# MCU.net
KiCad netlist of a schematic drawn in Altium Designer
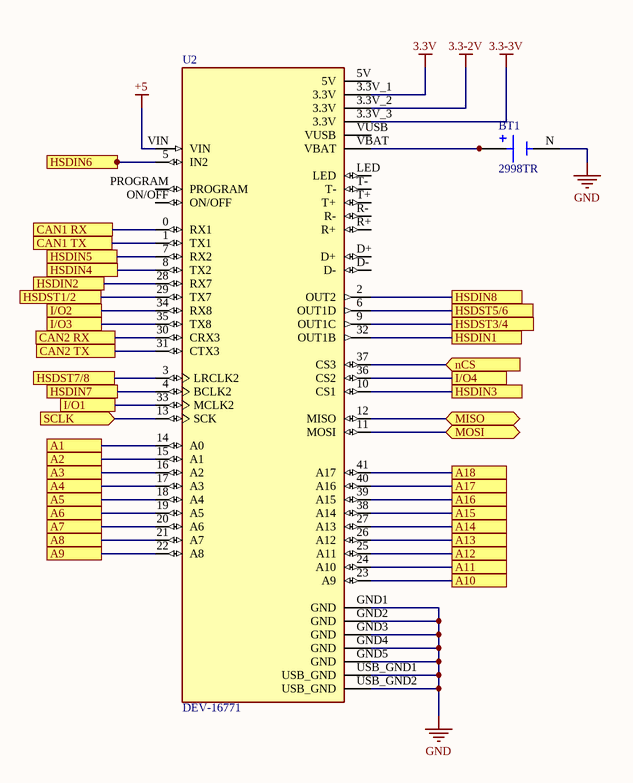
[diagram p0: MCU.SchDoc]

(export (version "E")
  (design (tool "Eeschema 10.0.6"))
  (components
    (comp (ref "BT1")
      (value "2998TR")
      (footprint "BAT_2998TR")
      (libsource (lib "Western Formula Racing") (part "2998TR"))
    )
    (comp (ref "U2")
      (value "DEV-16771")
      (footprint "MODULE_DEV-16771")
      (description "RT1062 Teensy 4.1 series ARMÂ® CortexÂ®-M7 MPU Embedded Evaluation Board")
      (fields (field (name "MF") "SparkFun Electronics"))
      (libsource (lib "Western Formula Racing") (part "DEV-16771"))
    )
  )
  (nets
    (net (code "1") (name "+5") (class "Default")
      (node (ref "U2") (pin "VIN") (pinfunction "VIN_VIN") (pintype "input"))
    )
    (net (code "2") (name "/A1") (class "Default")
      (node (ref "U2") (pin "14") (pinfunction "A0_14") (pintype "bidirectional"))
    )
    (net (code "3") (name "/A2") (class "Default")
      (node (ref "U2") (pin "15") (pinfunction "A1_15") (pintype "bidirectional"))
    )
    (net (code "4") (name "/A3") (class "Default")
      (node (ref "U2") (pin "16") (pinfunction "A2_16") (pintype "bidirectional"))
    )
    (net (code "5") (name "/A4") (class "Default")
      (node (ref "U2") (pin "17") (pinfunction "A3_17") (pintype "bidirectional"))
    )
    (net (code "6") (name "/A5") (class "Default")
      (node (ref "U2") (pin "18") (pinfunction "A4_18") (pintype "bidirectional"))
    )
    (net (code "7") (name "/A6") (class "Default")
      (node (ref "U2") (pin "19") (pinfunction "A5_19") (pintype "bidirectional"))
    )
    (net (code "8") (name "/A7") (class "Default")
      (node (ref "U2") (pin "20") (pinfunction "A6_20") (pintype "bidirectional"))
    )
    (net (code "9") (name "/A8") (class "Default")
      (node (ref "U2") (pin "21") (pinfunction "A7_21") (pintype "bidirectional"))
    )
    (net (code "10") (name "/A9") (class "Default")
      (node (ref "U2") (pin "22") (pinfunction "A8_22") (pintype "bidirectional"))
    )
    (net (code "11") (name "/A10") (class "Default")
      (node (ref "U2") (pin "23") (pinfunction "A9_23") (pintype "bidirectional"))
    )
    (net (code "12") (name "/A11") (class "Default")
      (node (ref "U2") (pin "24") (pinfunction "A10_24") (pintype "bidirectional"))
    )
    (net (code "13") (name "/A12") (class "Default")
      (node (ref "U2") (pin "25") (pinfunction "A11_25") (pintype "bidirectional"))
    )
    (net (code "14") (name "/A13") (class "Default")
      (node (ref "U2") (pin "26") (pinfunction "A12_26") (pintype "bidirectional"))
    )
    (net (code "15") (name "/A14") (class "Default")
      (node (ref "U2") (pin "27") (pinfunction "A13_27") (pintype "bidirectional"))
    )
    (net (code "16") (name "/A15") (class "Default")
      (node (ref "U2") (pin "38") (pinfunction "A14_38") (pintype "bidirectional"))
    )
    (net (code "17") (name "/A16") (class "Default")
      (node (ref "U2") (pin "39") (pinfunction "A15_39") (pintype "bidirectional"))
    )
    (net (code "18") (name "/A17") (class "Default")
      (node (ref "U2") (pin "40") (pinfunction "A16_40") (pintype "bidirectional"))
    )
    (net (code "19") (name "/A18") (class "Default")
      (node (ref "U2") (pin "41") (pinfunction "A17_41") (pintype "bidirectional"))
    )
    (net (code "20") (name "/CAN1 RX") (class "Default")
      (node (ref "U2") (pin "0") (pinfunction "RX1_0") (pintype "bidirectional"))
    )
    (net (code "21") (name "/CAN1 TX") (class "Default")
      (node (ref "U2") (pin "1") (pinfunction "TX1_1") (pintype "bidirectional"))
    )
    (net (code "22") (name "/CAN2 RX") (class "Default")
      (node (ref "U2") (pin "30") (pinfunction "CRX3_30") (pintype "bidirectional"))
    )
    (net (code "23") (name "/CAN2 TX") (class "Default")
      (node (ref "U2") (pin "31") (pinfunction "CTX3_31") (pintype "bidirectional"))
    )
    (net (code "24") (name "/HSDIN1") (class "Default")
      (node (ref "U2") (pin "32") (pinfunction "OUT1B_32") (pintype "output"))
    )
    (net (code "25") (name "/HSDIN2") (class "Default")
      (node (ref "U2") (pin "28") (pinfunction "RX7_28") (pintype "bidirectional"))
    )
    (net (code "26") (name "/HSDIN3") (class "Default")
      (node (ref "U2") (pin "10") (pinfunction "CS1_10") (pintype "bidirectional"))
    )
    (net (code "27") (name "/HSDIN4") (class "Default")
      (node (ref "U2") (pin "8") (pinfunction "TX2_8") (pintype "bidirectional"))
    )
    (net (code "28") (name "/HSDIN5") (class "Default")
      (node (ref "U2") (pin "7") (pinfunction "RX2_7") (pintype "bidirectional"))
    )
    (net (code "29") (name "/HSDIN6") (class "Default")
      (node (ref "U2") (pin "5") (pinfunction "IN2_5") (pintype "bidirectional"))
    )
    (net (code "30") (name "/HSDIN7") (class "Default")
      (node (ref "U2") (pin "4") (pinfunction "BCLK2_4") (pintype "bidirectional"))
    )
    (net (code "31") (name "/HSDIN8") (class "Default")
      (node (ref "U2") (pin "2") (pinfunction "OUT2_2") (pintype "output"))
    )
    (net (code "32") (name "/HSDST1{slash}2") (class "Default")
      (node (ref "U2") (pin "29") (pinfunction "TX7_29") (pintype "bidirectional"))
    )
    (net (code "33") (name "/HSDST3{slash}4") (class "Default")
      (node (ref "U2") (pin "9") (pinfunction "OUT1C_9") (pintype "output"))
    )
    (net (code "34") (name "/HSDST5{slash}6") (class "Default")
      (node (ref "U2") (pin "6") (pinfunction "OUT1D_6") (pintype "output"))
    )
    (net (code "35") (name "/HSDST7{slash}8") (class "Default")
      (node (ref "U2") (pin "3") (pinfunction "LRCLK2_3") (pintype "bidirectional"))
    )
    (net (code "36") (name "/I{slash}O1") (class "Default")
      (node (ref "U2") (pin "33") (pinfunction "MCLK2_33") (pintype "bidirectional"))
    )
    (net (code "37") (name "/I{slash}O2") (class "Default")
      (node (ref "U2") (pin "34") (pinfunction "RX8_34") (pintype "bidirectional"))
    )
    (net (code "38") (name "/I{slash}O3") (class "Default")
      (node (ref "U2") (pin "35") (pinfunction "TX8_35") (pintype "bidirectional"))
    )
    (net (code "39") (name "/I{slash}O4") (class "Default")
      (node (ref "U2") (pin "36") (pinfunction "CS2_36") (pintype "bidirectional"))
    )
    (net (code "40") (name "/MISO") (class "Default")
      (node (ref "U2") (pin "12") (pinfunction "MISO_12") (pintype "bidirectional"))
    )
    (net (code "41") (name "/MOSI") (class "Default")
      (node (ref "U2") (pin "11") (pinfunction "MOSI_11") (pintype "bidirectional"))
    )
    (net (code "42") (name "/SCLK") (class "Default")
      (node (ref "U2") (pin "13") (pinfunction "SCK_13") (pintype "bidirectional"))
    )
    (net (code "43") (name "/nCS") (class "Default")
      (node (ref "U2") (pin "37") (pinfunction "CS3_37") (pintype "bidirectional"))
    )
    (net (code "44") (name "3.3-2V") (class "Default")
      (node (ref "U2") (pin "3.3V_2") (pinfunction "3.3V_3.3V_2") (pintype "power_in"))
    )
    (net (code "45") (name "3.3-3V") (class "Default")
      (node (ref "U2") (pin "3.3V_3") (pinfunction "3.3V_3.3V_3") (pintype "power_in"))
    )
    (net (code "46") (name "3.3V") (class "Default")
      (node (ref "U2") (pin "3.3V_1") (pinfunction "3.3V_3.3V_1") (pintype "power_in"))
    )
    (net (code "47") (name "GND") (class "Default")
      (node (ref "BT1") (pin "N") (pinfunction "NEG_N") (pintype "passive"))
      (node (ref "U2") (pin "GND1") (pinfunction "GND_GND1") (pintype "power_in"))
      (node (ref "U2") (pin "GND2") (pinfunction "GND_GND2") (pintype "power_in"))
      (node (ref "U2") (pin "GND3") (pinfunction "GND_GND3") (pintype "power_in"))
      (node (ref "U2") (pin "GND4") (pinfunction "GND_GND4") (pintype "power_in"))
      (node (ref "U2") (pin "GND5") (pinfunction "GND_GND5") (pintype "power_in"))
      (node (ref "U2") (pin "USB_GND1") (pinfunction "USB_GND_USB_GND1") (pintype "power_in"))
      (node (ref "U2") (pin "USB_GND2") (pinfunction "USB_GND_USB_GND2") (pintype "power_in"))
    )
    (net (code "48") (name "Net-(BT1-POS-PadP1)") (class "Default")
      (node (ref "BT1") (pin "P1") (pinfunction "POS_P1") (pintype "passive"))
      (node (ref "BT1") (pin "P2") (pinfunction "POS_P2") (pintype "passive"))
      (node (ref "U2") (pin "VBAT") (pinfunction "VBAT_VBAT") (pintype "passive"))
    )
    (net (code "49") (name "unconnected-(U2-Pad5V)") (class "Default")
      (node (ref "U2") (pin "5V") (pinfunction "5V_5V") (pintype "power_in"))
    )
    (net (code "50") (name "unconnected-(U2-PadD+)") (class "Default")
      (node (ref "U2") (pin "D+") (pinfunction "D+_D+") (pintype "bidirectional"))
    )
    (net (code "51") (name "unconnected-(U2-PadD-)") (class "Default")
      (node (ref "U2") (pin "D-") (pinfunction "D-_D-") (pintype "bidirectional"))
    )
    (net (code "52") (name "unconnected-(U2-PadLED)") (class "Default")
      (node (ref "U2") (pin "LED") (pinfunction "LED_LED") (pintype "bidirectional"))
    )
    (net (code "53") (name "unconnected-(U2-PadON{slash}OFF)") (class "Default")
      (node (ref "U2") (pin "ON/OFF") (pinfunction "ON/OFF_ON/OFF") (pintype "bidirectional"))
    )
    (net (code "54") (name "unconnected-(U2-PadPROGRAM)") (class "Default")
      (node (ref "U2") (pin "PROGRAM") (pinfunction "PROGRAM_PROGRAM") (pintype "bidirectional"))
    )
    (net (code "55") (name "unconnected-(U2-PadR+)") (class "Default")
      (node (ref "U2") (pin "R+") (pinfunction "R+_R+") (pintype "bidirectional"))
    )
    (net (code "56") (name "unconnected-(U2-PadR-)") (class "Default")
      (node (ref "U2") (pin "R-") (pinfunction "R-_R-") (pintype "bidirectional"))
    )
    (net (code "57") (name "unconnected-(U2-PadT+)") (class "Default")
      (node (ref "U2") (pin "T+") (pinfunction "T+_T+") (pintype "bidirectional"))
    )
    (net (code "58") (name "unconnected-(U2-PadT-)") (class "Default")
      (node (ref "U2") (pin "T-") (pinfunction "T-_T-") (pintype "bidirectional"))
    )
    (net (code "59") (name "unconnected-(U2-PadVUSB)") (class "Default")
      (node (ref "U2") (pin "VUSB") (pinfunction "VUSB_VUSB") (pintype "passive"))
    )
  )
)
